# HV_DRV_ADHV4702.net
KiCad netlist of a schematic drawn in Altium Designer
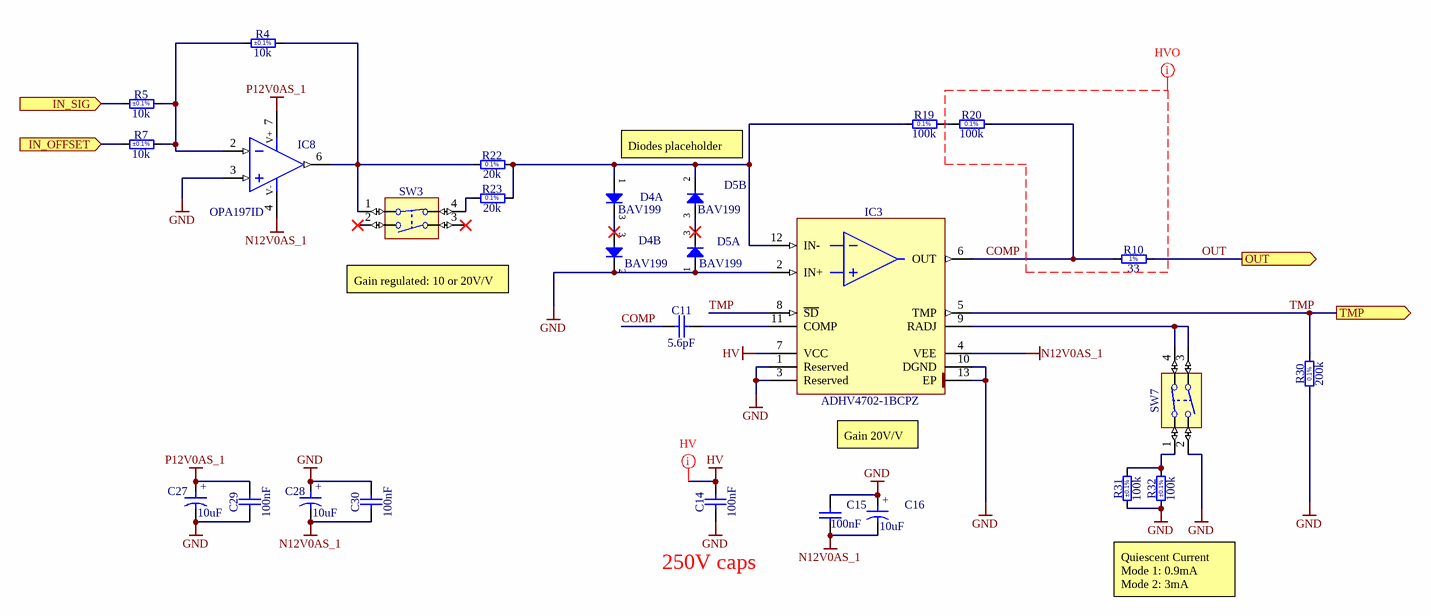
[diagram p0: HV_DRV_ADHV4702.SchDoc]

(export (version "E")
  (design (tool "Eeschema 10.0.6"))
  (components
    (comp (ref "C11")
      (value "5.6pF")
      (footprint "CAPC2012X135N")
      (description "Non-polarised capacitor")
      (fields (field (name "PART NUMBER") "CC0805_5.6PF_250V_0.25PF_NP0") (field (name "VOLTAGE") "250V"))
      (libsource (lib "Capacitors") (part "Capacitor - non polarized"))
    )
    (comp (ref "C14")
      (value "100nF")
      (footprint "CAPC4720X215N")
      (description "Non-polarised capacitor")
      (fields
        (field (name "PART NUMBER") "CC1808_100NF_630V_10%_X7R")
        (field (name "VOLTAGE") "630V")
        (field (name "AUTHOR") "CERN DEM MR")
      )
      (libsource (lib "Capacitors") (part "Capacitor - non polarized"))
    )
    (comp (ref "C15")
      (value "100nF")
      (footprint "CAPC1005X55N")
      (description "Non-polarised capacitor")
      (fields
        (field (name "PART NUMBER") "CC0402_100NF_16V_10%_X5R")
        (field (name "VOLTAGE") "16V")
        (field (name "AUTHOR") "CERN DEM JLC")
      )
      (libsource (lib "Capacitors") (part "Capacitor - non polarized"))
    )
    (comp (ref "C16")
      (value "10uF")
      (footprint "CAPMP3216X180N")
      (description "Polarised capacitor")
      (fields
        (field (name "PART NUMBER") "CTE3216-18_10UF_16V_20%_AVX_TCJ")
        (field (name "VOLTAGE") "16V")
        (field (name "AUTHOR") "CERN DEM JLC")
      )
      (libsource (lib "Capacitors") (part "Capacitor - polarized"))
    )
    (comp (ref "C27")
      (value "10uF")
      (footprint "CAPMP3216X180N")
      (description "Polarised capacitor")
      (fields
        (field (name "PART NUMBER") "CTE3216-18_10UF_16V_20%_AVX_TCJ")
        (field (name "VOLTAGE") "16V")
        (field (name "AUTHOR") "CERN DEM JLC")
      )
      (libsource (lib "Capacitors") (part "Capacitor - polarized"))
    )
    (comp (ref "C28")
      (value "10uF")
      (footprint "CAPMP3216X180N")
      (description "Polarised capacitor")
      (fields
        (field (name "PART NUMBER") "CTE3216-18_10UF_16V_20%_AVX_TCJ")
        (field (name "VOLTAGE") "16V")
        (field (name "AUTHOR") "CERN DEM JLC")
      )
      (libsource (lib "Capacitors") (part "Capacitor - polarized"))
    )
    (comp (ref "C29")
      (value "100nF")
      (footprint "CAPC1608X87N")
      (description "Non-polarised capacitor")
      (fields
        (field (name "PART NUMBER") "CC0603_100NF_50V_10%_X7R")
        (field (name "VOLTAGE") "50V")
        (field (name "AUTHOR") "CERN DEM JLC")
      )
      (libsource (lib "Capacitors") (part "Capacitor - non polarized"))
    )
    (comp (ref "C30")
      (value "100nF")
      (footprint "CAPC1608X87N")
      (description "Non-polarised capacitor")
      (fields
        (field (name "PART NUMBER") "CC0603_100NF_50V_10%_X7R")
        (field (name "VOLTAGE") "50V")
        (field (name "AUTHOR") "CERN DEM JLC")
      )
      (libsource (lib "Capacitors") (part "Capacitor - non polarized"))
    )
    (comp (ref "D4")
      (value "BAV199")
      (footprint "SOT95P240X110-3N")
      (description "Serial Diode")
      (fields
        (field (name "VOLTAGE") "75V")
        (field (name "POWER") "250mW")
        (field (name "AUTHOR") "CERN DEM JMW")
      )
      (libsource (lib "ICs And Semiconductors") (part "Diode x2 A1C3_A3C2"))
    )
    (comp (ref "D5")
      (value "BAV199")
      (footprint "SOT95P240X110-3N")
      (description "Serial Diode")
      (fields
        (field (name "VOLTAGE") "75V")
        (field (name "POWER") "250mW")
        (field (name "AUTHOR") "CERN DEM JMW")
      )
      (libsource (lib "ICs And Semiconductors") (part "Diode x2 A1C3_A3C2"))
    )
    (comp (ref "IC3")
      (value "ADHV4702-1BCPZ")
      (footprint "QFN170P700X700X80-13N-S290")
      (description "24V to 220V Precision Operational Amplifier")
      (fields (field (name "MANUFACTURER") "ANALOG DEVICES") (field (name "AUTHOR") "CERN DEM BC"))
      (libsource (lib "ICs And Semiconductors") (part "ADHV4702-1"))
    )
    (comp (ref "IC8")
      (value "OPA197ID")
      (footprint "SOIC127P600X175-8N")
      (description "Operational Amplifier")
      (fields (field (name "MANUFACTURER") "TEXAS INSTRUMENTS") (field (name "AUTHOR") "CERN DEM MR"))
      (libsource (lib "ICs And Semiconductors") (part "Operational Amplifier Type1"))
    )
    (comp (ref "R4")
      (value "10k")
      (footprint "RESC1608X55N")
      (description "Resistor - 0.1%")
      (fields
        (field (name "TOLERANCE") "±0.1%")
        (field (name "PART NUMBER") "R0603_10K_0.1%_0.063W_10PPM")
        (field (name "POWER") "0.063W")
        (field (name "AUTHOR") "CERN DEM JLC")
      )
      (libsource (lib "Resistors") (part "Resistor - 0.1%"))
    )
    (comp (ref "R5")
      (value "10k")
      (footprint "RESC1608X55N")
      (description "Resistor - 0.1%")
      (fields
        (field (name "TOLERANCE") "±0.1%")
        (field (name "PART NUMBER") "R0603_10K_0.1%_0.063W_10PPM")
        (field (name "POWER") "0.063W")
        (field (name "AUTHOR") "CERN DEM JLC")
      )
      (libsource (lib "Resistors") (part "Resistor - 0.1%"))
    )
    (comp (ref "R7")
      (value "10k")
      (footprint "RESC1608X55N")
      (description "Resistor - 0.1%")
      (fields
        (field (name "TOLERANCE") "±0.1%")
        (field (name "PART NUMBER") "R0603_10K_0.1%_0.063W_10PPM")
        (field (name "POWER") "0.063W")
        (field (name "AUTHOR") "CERN DEM JLC")
      )
      (libsource (lib "Resistors") (part "Resistor - 0.1%"))
    )
    (comp (ref "R10")
      (value "33")
      (footprint "RESC2012X60N")
      (description "Resistor - 1%")
      (fields
        (field (name "PART NUMBER") "R0805_33R_1%_0.125W_100PPM")
        (field (name "POWER") "0.125W")
        (field (name "AUTHOR") "CERN DEM JLC")
      )
      (libsource (lib "Resistors") (part "Resistor - 1%"))
    )
    (comp (ref "R19")
      (value "100k")
      (footprint "RESC2012X60N")
      (description "Resistor - 0.1%")
      (fields
        (field (name "PART NUMBER") "R0805_100K_0.1%_0.1W_10PPM")
        (field (name "POWER") "0.1W")
        (field (name "AUTHOR") "CERN DEM JLC")
      )
      (libsource (lib "") (part "Resistor - 0.1%_1"))
    )
    (comp (ref "R20")
      (value "100k")
      (footprint "RESC2012X60N")
      (description "Resistor - 0.1%")
      (fields
        (field (name "PART NUMBER") "R0805_100K_0.1%_0.1W_10PPM")
        (field (name "POWER") "0.1W")
        (field (name "AUTHOR") "CERN DEM JLC")
      )
      (libsource (lib "") (part "Resistor - 0.1%_1"))
    )
    (comp (ref "R22")
      (value "20k")
      (footprint "RESC1608X55N")
      (description "Resistor - 0.1%")
      (fields
        (field (name "PART NUMBER") "R0603_20K_0.1%_0.063W_10PPM")
        (field (name "POWER") "0.063W")
        (field (name "AUTHOR") "CERN DEM JLC")
      )
      (libsource (lib "Resistors") (part "Resistor - 0.1%"))
    )
    (comp (ref "R23")
      (value "20k")
      (footprint "RESC1608X55N")
      (description "Resistor - 0.1%")
      (fields
        (field (name "PART NUMBER") "R0603_20K_0.1%_0.063W_10PPM")
        (field (name "POWER") "0.063W")
        (field (name "AUTHOR") "CERN DEM JLC")
      )
      (libsource (lib "Resistors") (part "Resistor - 0.1%"))
    )
    (comp (ref "R30")
      (value "200k")
      (footprint "RESC1608X55N")
      (description "Resistor - 0.1%")
      (fields
        (field (name "PART NUMBER") "R0603_200K_0.1%_0.063W_10PPM")
        (field (name "POWER") "0.063W")
        (field (name "AUTHOR") "CERN DEM MR")
      )
      (libsource (lib "Resistors") (part "Resistor - 0.1%"))
    )
    (comp (ref "R31")
      (value "100k")
      (footprint "RESC1005X35N")
      (description "Resistor - 0.1%")
      (fields
        (field (name "TOLERANCE") "±0.1%")
        (field (name "PART NUMBER") "R0402_100K_0.1%_0.063W_25PPM")
        (field (name "POWER") "0.063W")
        (field (name "AUTHOR") "CERN DEM JMW")
      )
      (libsource (lib "Resistors") (part "Resistor - 0.1%"))
    )
    (comp (ref "R32")
      (value "100k")
      (footprint "RESC1005X35N")
      (description "Resistor - 0.1%")
      (fields
        (field (name "TOLERANCE") "±0.1%")
        (field (name "PART NUMBER") "R0402_100K_0.1%_0.063W_25PPM")
        (field (name "POWER") "0.063W")
        (field (name "AUTHOR") "CERN DEM JMW")
      )
      (libsource (lib "Resistors") (part "Resistor - 0.1%"))
    )
    (comp (ref "SW3")
      (value "Switch")
      (footprint "SW_CTS_204-121ST")
      (description "2x SPST DIP Switch 1NO + 1NF")
      (fields
        (field (name "PART NUMBER") "SW_CTS_204-121ST")
        (field (name "MANUFACTURER") "CTS")
        (field (name "AUTHOR") "CERN DEM JLC")
      )
      (libsource (lib "Eletro-mechanical") (part "SW_CTS_204-121ST"))
    )
    (comp (ref "SW7")
      (value "Switch")
      (footprint "SW_CTS_204-121ST")
      (description "2x SPST DIP Switch 1NO + 1NF")
      (fields
        (field (name "PART NUMBER") "SW_CTS_204-121ST")
        (field (name "MANUFACTURER") "CTS")
        (field (name "AUTHOR") "CERN DEM JLC")
      )
      (libsource (lib "") (part "SW_CTS_204-121ST_1"))
    )
  )
  (nets
    (net (code "2") (name "/COMP") (class "Default")
      (node (ref "C11") (pin "1") (pinfunction "1_1") (pintype "passive"))
      (node (ref "IC3") (pin "6") (pinfunction "OUT_6") (pintype "output"))
      (node (ref "R10") (pin "1") (pinfunction "1_1") (pintype "passive"))
      (node (ref "R20") (pin "2") (pinfunction "2_2") (pintype "passive"))
    )
    (net (code "3") (name "/IN_OFFSET") (class "Default")
      (node (ref "R7") (pin "1") (pinfunction "1_1") (pintype "passive"))
    )
    (net (code "4") (name "/IN_SIG") (class "Default")
      (node (ref "R5") (pin "1") (pinfunction "1_1") (pintype "passive"))
    )
    (net (code "5") (name "/OUT") (class "Default")
      (node (ref "R10") (pin "2") (pinfunction "2_2") (pintype "passive"))
    )
    (net (code "6") (name "/TMP") (class "Default")
      (node (ref "IC3") (pin "5") (pinfunction "TMP_5") (pintype "output"))
      (node (ref "IC3") (pin "8") (pinfunction "~{SD}_8") (pintype "input"))
      (node (ref "R30") (pin "2") (pinfunction "2_2") (pintype "passive"))
    )
    (net (code "7") (name "GND") (class "Default")
      (node (ref "C14") (pin "1") (pinfunction "1_1") (pintype "passive"))
      (node (ref "C15") (pin "2") (pinfunction "2_2") (pintype "passive"))
      (node (ref "C16") (pin "1") (pinfunction "1_1") (pintype "passive"))
      (node (ref "C27") (pin "2") (pinfunction "2_2") (pintype "passive"))
      (node (ref "C28") (pin "1") (pinfunction "1_1") (pintype "passive"))
      (node (ref "C29") (pin "1") (pinfunction "1_1") (pintype "passive"))
      (node (ref "C30") (pin "2") (pinfunction "2_2") (pintype "passive"))
      (node (ref "D4") (pin "2") (pinfunction "C_2") (pintype "passive"))
      (node (ref "D5") (pin "1") (pinfunction "A_1") (pintype "passive"))
      (node (ref "IC3") (pin "1") (pinfunction "Reserved_1") (pintype "passive"))
      (node (ref "IC3") (pin "10") (pinfunction "DGND_10") (pintype "power_in"))
      (node (ref "IC3") (pin "13") (pinfunction "EP_13") (pintype "passive"))
      (node (ref "IC3") (pin "2") (pinfunction "IN+_2") (pintype "input"))
      (node (ref "IC3") (pin "3") (pinfunction "Reserved_3") (pintype "passive"))
      (node (ref "IC8") (pin "3") (pinfunction "IN+_3") (pintype "input"))
      (node (ref "R30") (pin "1") (pinfunction "1_1") (pintype "passive"))
      (node (ref "R31") (pin "1") (pinfunction "1_1") (pintype "passive"))
      (node (ref "R32") (pin "1") (pinfunction "1_1") (pintype "passive"))
      (node (ref "SW7") (pin "2") (pinfunction "2_2") (pintype "bidirectional"))
    )
    (net (code "8") (name "HV") (class "Default")
      (node (ref "C14") (pin "2") (pinfunction "2_2") (pintype "passive"))
      (node (ref "IC3") (pin "7") (pinfunction "VCC_7") (pintype "power_in"))
    )
    (net (code "9") (name "N12V0AS_1") (class "Default")
      (node (ref "C15") (pin "1") (pinfunction "1_1") (pintype "passive"))
      (node (ref "C16") (pin "2") (pinfunction "2_2") (pintype "passive"))
      (node (ref "C28") (pin "2") (pinfunction "2_2") (pintype "passive"))
      (node (ref "C30") (pin "1") (pinfunction "1_1") (pintype "passive"))
      (node (ref "IC3") (pin "4") (pinfunction "VEE_4") (pintype "power_in"))
      (node (ref "IC8") (pin "4") (pinfunction "V-_4") (pintype "power_in"))
    )
    (net (code "10") (name "Net-(D4A-A)") (class "Default")
      (node (ref "D4") (pin "1") (pinfunction "A_1") (pintype "passive"))
      (node (ref "D5") (pin "2") (pinfunction "C_2") (pintype "passive"))
      (node (ref "IC3") (pin "12") (pinfunction "IN-_12") (pintype "input"))
      (node (ref "R19") (pin "1") (pinfunction "1_1") (pintype "passive"))
      (node (ref "R22") (pin "2") (pinfunction "2_2") (pintype "passive"))
      (node (ref "R23") (pin "2") (pinfunction "2_2") (pintype "passive"))
    )
    (net (code "11") (name "Net-(IC3-COMP)") (class "Default")
      (node (ref "C11") (pin "2") (pinfunction "2_2") (pintype "passive"))
      (node (ref "IC3") (pin "11") (pinfunction "COMP_11") (pintype "passive"))
    )
    (net (code "12") (name "Net-(IC3-RADJ)") (class "Default")
      (node (ref "IC3") (pin "9") (pinfunction "RADJ_9") (pintype "passive"))
      (node (ref "SW7") (pin "3") (pinfunction "3_3") (pintype "bidirectional"))
      (node (ref "SW7") (pin "4") (pinfunction "4_4") (pintype "bidirectional"))
    )
    (net (code "13") (name "Net-(IC8-IN-)") (class "Default")
      (node (ref "IC8") (pin "2") (pinfunction "IN-_2") (pintype "input"))
      (node (ref "R4") (pin "1") (pinfunction "1_1") (pintype "passive"))
      (node (ref "R5") (pin "2") (pinfunction "2_2") (pintype "passive"))
      (node (ref "R7") (pin "2") (pinfunction "2_2") (pintype "passive"))
    )
    (net (code "14") (name "Net-(IC8-OUT)") (class "Default")
      (node (ref "IC8") (pin "6") (pinfunction "OUT_6") (pintype "output"))
      (node (ref "R22") (pin "1") (pinfunction "1_1") (pintype "passive"))
      (node (ref "R4") (pin "2") (pinfunction "2_2") (pintype "passive"))
      (node (ref "SW3") (pin "1") (pinfunction "1_1") (pintype "bidirectional"))
    )
    (net (code "15") (name "Net-(R19-Pad2)") (class "Default")
      (node (ref "R19") (pin "2") (pinfunction "2_2") (pintype "passive"))
      (node (ref "R20") (pin "1") (pinfunction "1_1") (pintype "passive"))
    )
    (net (code "16") (name "Net-(R23-Pad1)") (class "Default")
      (node (ref "R23") (pin "1") (pinfunction "1_1") (pintype "passive"))
      (node (ref "SW3") (pin "4") (pinfunction "4_4") (pintype "bidirectional"))
    )
    (net (code "17") (name "Net-(R31-Pad2)") (class "Default")
      (node (ref "R31") (pin "2") (pinfunction "2_2") (pintype "passive"))
      (node (ref "R32") (pin "2") (pinfunction "2_2") (pintype "passive"))
      (node (ref "SW7") (pin "1") (pinfunction "1_1") (pintype "bidirectional"))
    )
    (net (code "18") (name "P12V0AS_1") (class "Default")
      (node (ref "C27") (pin "1") (pinfunction "1_1") (pintype "passive"))
      (node (ref "C29") (pin "2") (pinfunction "2_2") (pintype "passive"))
      (node (ref "IC8") (pin "7") (pinfunction "V+_7") (pintype "power_in"))
    )
    (net (code "19") (name "unconnected-(D4A-COMAC-Pad3)") (class "Default")
      (node (ref "D4") (pin "3") (pinfunction "COMAC_3") (pintype "passive+no_connect"))
    )
    (net (code "20") (name "unconnected-(D5A-COMAC-Pad3)") (class "Default")
      (node (ref "D5") (pin "3") (pinfunction "COMAC_3") (pintype "passive+no_connect"))
    )
    (net (code "21") (name "unconnected-(SW3-Pad2)") (class "Default")
      (node (ref "SW3") (pin "2") (pinfunction "2_2") (pintype "bidirectional+no_connect"))
    )
    (net (code "22") (name "unconnected-(SW3-Pad3)") (class "Default")
      (node (ref "SW3") (pin "3") (pinfunction "3_3") (pintype "bidirectional+no_connect"))
    )
  )
)
